# MotorControl.net
KiCad netlist of a schematic drawn in Altium Designer
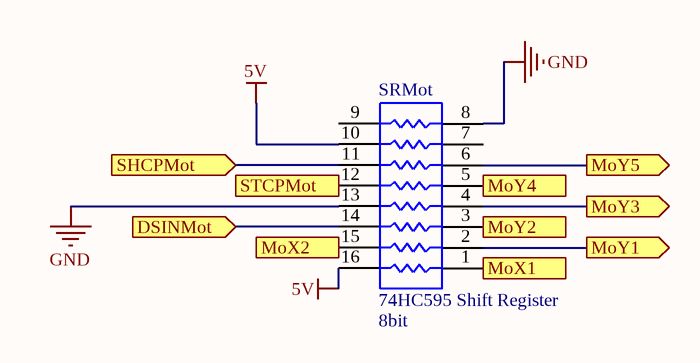
[diagram p0: MotorControl.SchDoc]

(export (version "E")
  (design (tool "Eeschema 10.0.6"))
  (components
    (comp (ref "SRMot")
      (value "74HC595 Shift Register")
      (footprint "SO-16_L")
      (description "Isolated Resistor Network")
      (fields (field (name "ALTIUM_VALUE") "8bit") (field (name "PUBLISHER") "Altium Limited"))
      (libsource (lib "Miscellaneous Devices") (part "Res Pack3"))
    )
  )
  (nets
    (net (code "1") (name "/DSINMot") (class "Default")
      (node (ref "SRMot") (pin "14") (pinfunction "14_14") (pintype "passive"))
    )
    (net (code "2") (name "/MoX1") (class "Default")
      (node (ref "SRMot") (pin "1") (pinfunction "1_1") (pintype "passive"))
    )
    (net (code "3") (name "/MoX2") (class "Default")
      (node (ref "SRMot") (pin "15") (pinfunction "15_15") (pintype "passive"))
    )
    (net (code "4") (name "/MoY1") (class "Default")
      (node (ref "SRMot") (pin "2") (pinfunction "2_2") (pintype "passive"))
    )
    (net (code "5") (name "/MoY2") (class "Default")
      (node (ref "SRMot") (pin "3") (pinfunction "3_3") (pintype "passive"))
    )
    (net (code "6") (name "/MoY3") (class "Default")
      (node (ref "SRMot") (pin "4") (pinfunction "4_4") (pintype "passive"))
    )
    (net (code "7") (name "/MoY4") (class "Default")
      (node (ref "SRMot") (pin "5") (pinfunction "5_5") (pintype "passive"))
    )
    (net (code "8") (name "/MoY5") (class "Default")
      (node (ref "SRMot") (pin "6") (pinfunction "6_6") (pintype "passive"))
    )
    (net (code "9") (name "/SHCPMot") (class "Default")
      (node (ref "SRMot") (pin "11") (pinfunction "11_11") (pintype "passive"))
    )
    (net (code "10") (name "/STCPMot") (class "Default")
      (node (ref "SRMot") (pin "12") (pinfunction "12_12") (pintype "passive"))
    )
    (net (code "11") (name "5V") (class "Default")
      (node (ref "SRMot") (pin "10") (pinfunction "10_10") (pintype "passive"))
      (node (ref "SRMot") (pin "16") (pinfunction "16_16") (pintype "passive"))
    )
    (net (code "12") (name "GND") (class "Default")
      (node (ref "SRMot") (pin "13") (pinfunction "13_13") (pintype "passive"))
      (node (ref "SRMot") (pin "8") (pinfunction "8_8") (pintype "passive"))
    )
    (net (code "13") (name "unconnected-(SRMot-Pad7)") (class "Default")
      (node (ref "SRMot") (pin "7") (pinfunction "7_7") (pintype "passive"))
    )
    (net (code "14") (name "unconnected-(SRMot-Pad9)") (class "Default")
      (node (ref "SRMot") (pin "9") (pinfunction "9_9") (pintype "passive"))
    )
  )
)
